# Thermostat_16CH.net
KiCad netlist of a schematic drawn in Altium Designer
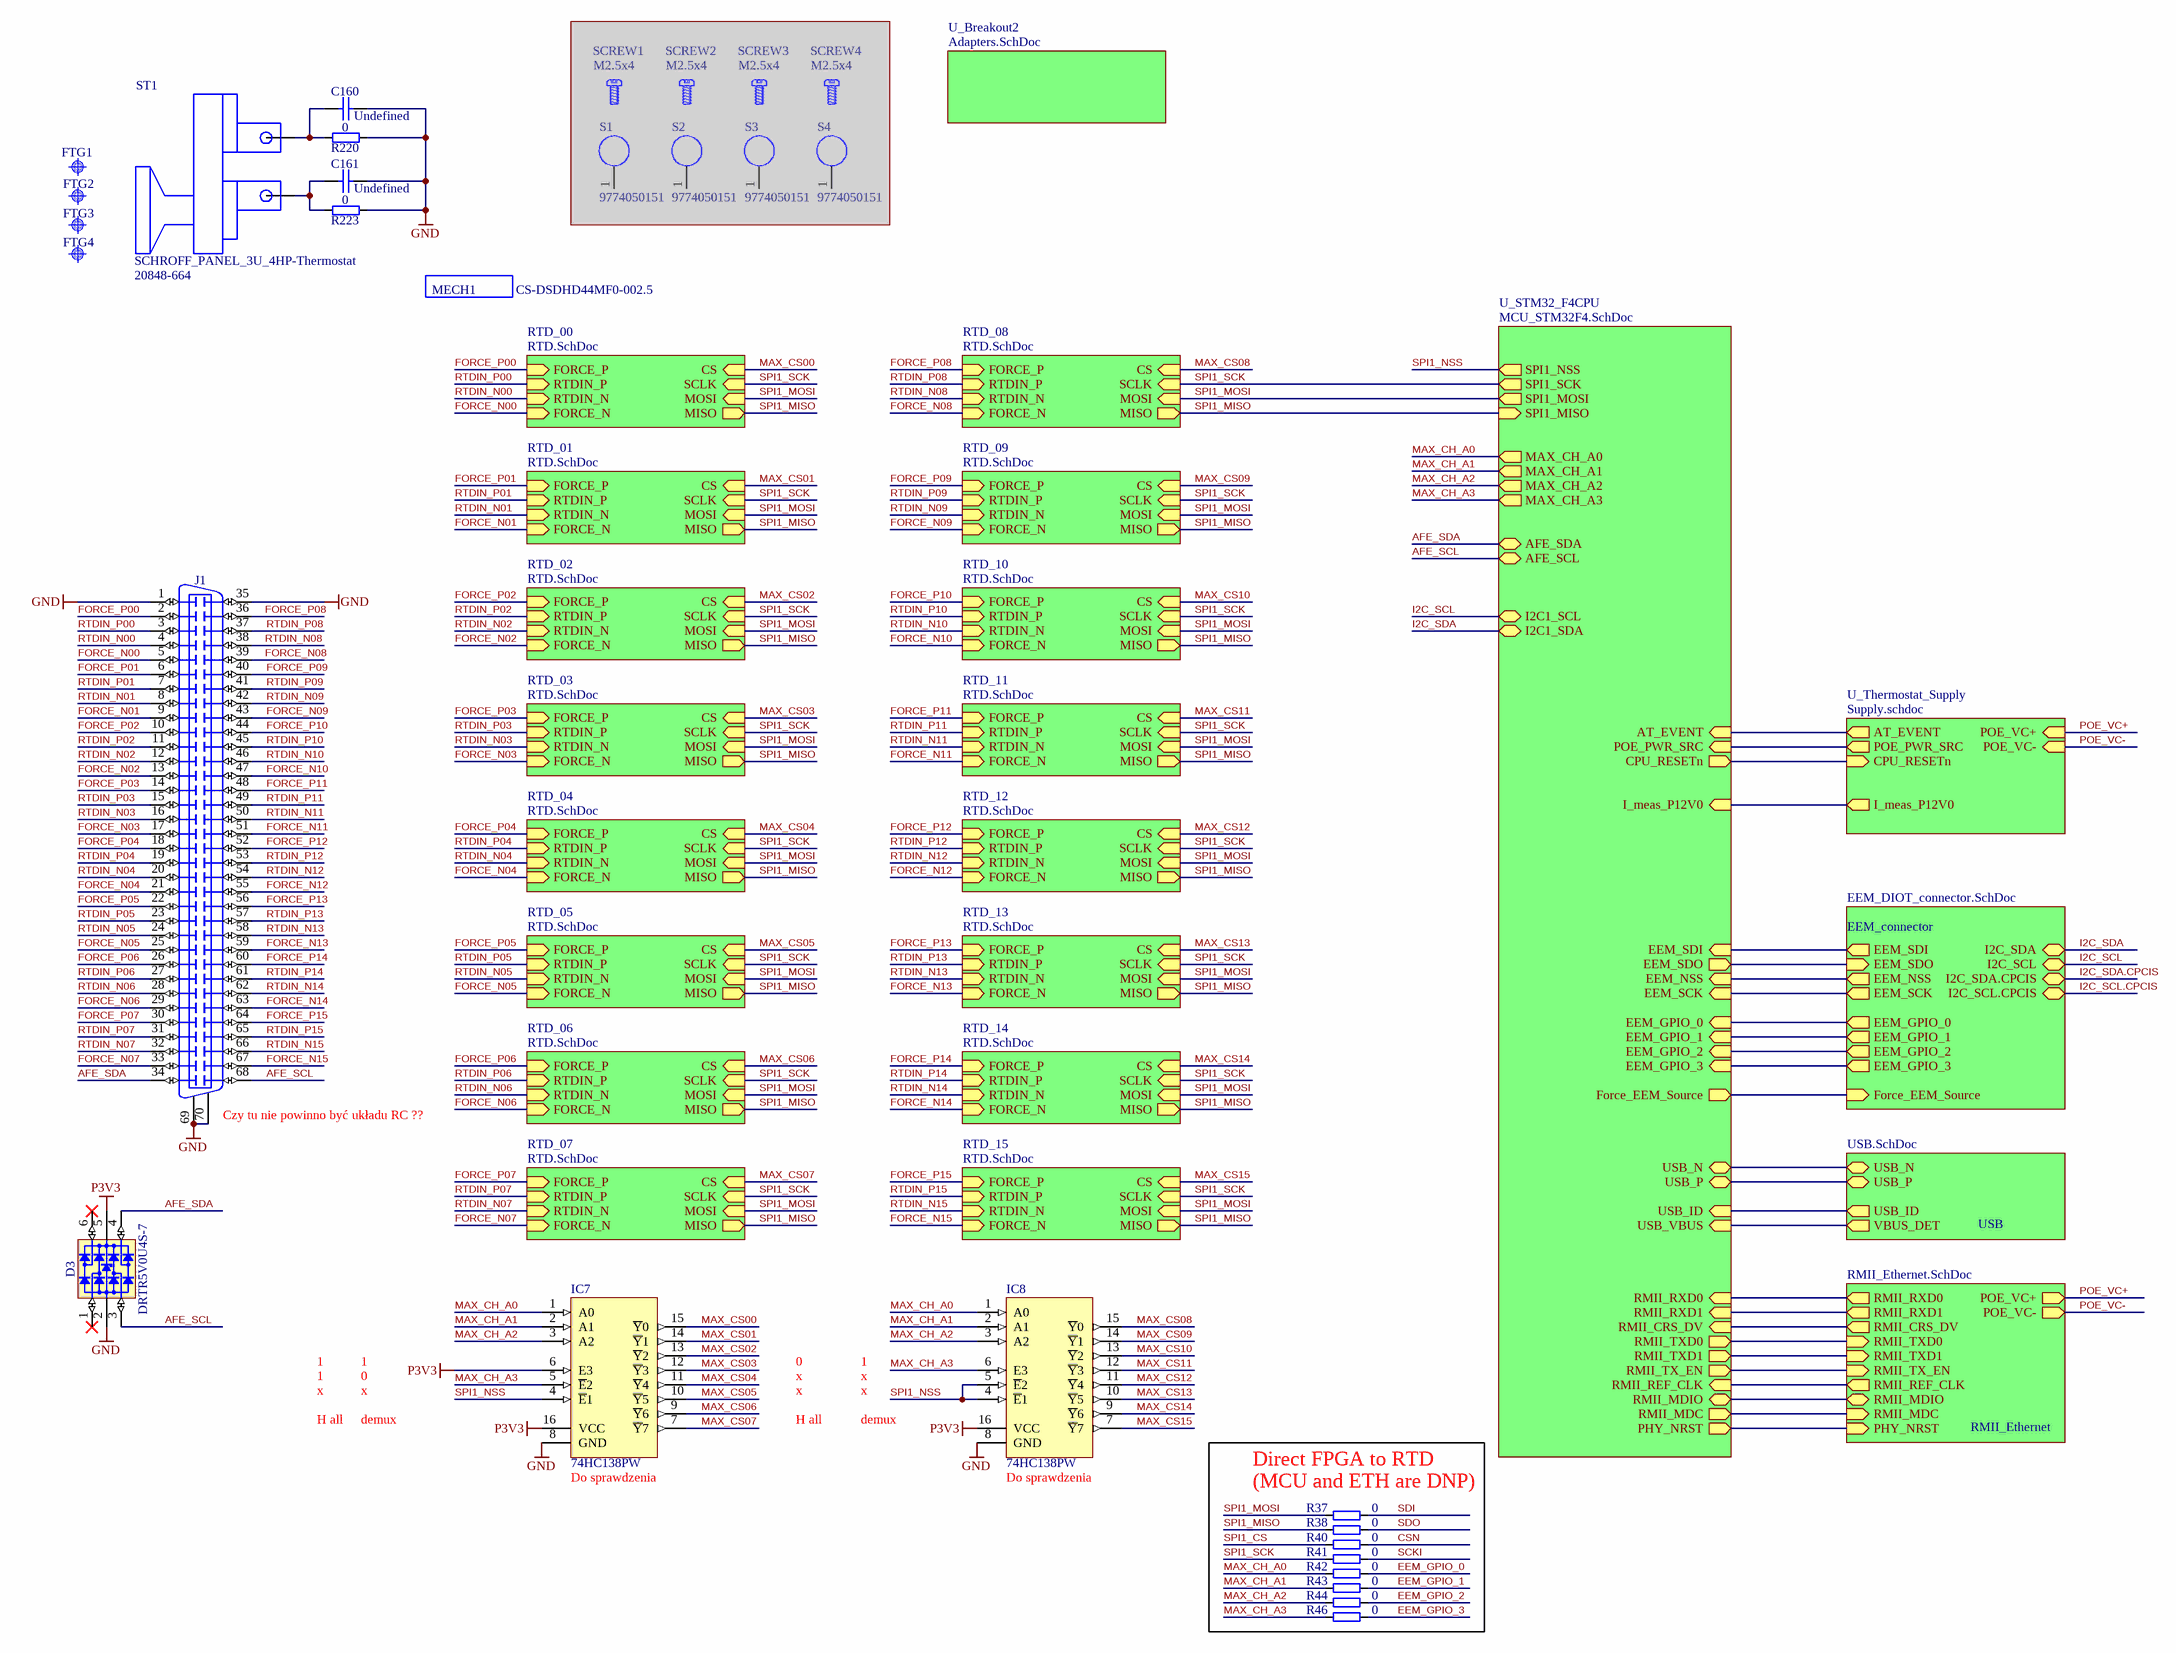
[diagram p0: Thermostat_16CH.SchDoc]

(export (version "E")
  (design (tool "Eeschema 10.0.6"))
  (components
    (comp (ref "C160")
      (value "Undefined")
      (footprint "CAPC2012X135N")
      (description "Non-polarised capacitor")
      (fields (field (name "PART NUMBER") "CC0805_NO-VALUE") (field (name "AUTHOR") "CERN DEM JLC"))
      (libsource (lib "Capacitors") (part "Capacitor - non polarized"))
    )
    (comp (ref "C161")
      (value "Undefined")
      (footprint "CAPC2012X135N")
      (description "Non-polarised capacitor")
      (fields (field (name "PART NUMBER") "CC0805_NO-VALUE") (field (name "AUTHOR") "CERN DEM JLC"))
      (libsource (lib "Capacitors") (part "Capacitor - non polarized"))
    )
    (comp (ref "D3")
      (value "DRTR5V0U4S-7")
      (footprint "SOT65P210X110-6N")
      (description "Integrated Quad Ultra-Low Capacitance ESD Protection")
      (fields (field (name "MANUFACTURER") "DIODES") (field (name "AUTHOR") "GK"))
      (libsource (lib "Diodes") (part "D_TVS_DRTR5V0U4S-7"))
    )
    (comp (ref "FTG1")
      (value "Use only in PCB")
      (footprint "FIDUCIAL_TOP_S100-200")
      (description "Fiducial Target")
      (fields (field (name "PART NUMBER") "FIDUCIAL_TARGET_S100-200") (field (name "AUTHOR") "CERN DEM JLC"))
      (libsource (lib "Eletro-mechanical") (part "Fiducial Target"))
    )
    (comp (ref "FTG2")
      (value "Use only in PCB")
      (footprint "FIDUCIAL_TOP_S100-200")
      (description "Fiducial Target")
      (fields (field (name "PART NUMBER") "FIDUCIAL_TARGET_S100-200") (field (name "AUTHOR") "CERN DEM JLC"))
      (libsource (lib "Eletro-mechanical") (part "Fiducial Target"))
    )
    (comp (ref "FTG3")
      (value "Use only in PCB")
      (footprint "FIDUCIAL_TOP_S100-200")
      (description "Fiducial Target")
      (fields (field (name "PART NUMBER") "FIDUCIAL_TARGET_S100-200") (field (name "AUTHOR") "CERN DEM JLC"))
      (libsource (lib "Eletro-mechanical") (part "Fiducial Target"))
    )
    (comp (ref "FTG4")
      (value "Use only in PCB")
      (footprint "FIDUCIAL_TOP_S100-200")
      (description "Fiducial Target")
      (fields (field (name "PART NUMBER") "FIDUCIAL_TARGET_S100-200") (field (name "AUTHOR") "CERN DEM JLC"))
      (libsource (lib "Eletro-mechanical") (part "Fiducial Target"))
    )
    (comp (ref "IC7")
      (value "74HC138PW")
      (footprint "SOP65P640X110-16N")
      (description "3-Line to 8-Line Decoder/Demultiplexer")
      (fields (field (name "MANUFACTURER") "NXP SEMICONDUCTORS") (field (name "AUTHOR") "CERN DEM JLC"))
      (libsource (lib "ICs And Semiconductors") (part "74138_a"))
    )
    (comp (ref "IC8")
      (value "74HC138PW")
      (footprint "SOP65P640X110-16N")
      (description "3-Line to 8-Line Decoder/Demultiplexer")
      (fields (field (name "MANUFACTURER") "NXP SEMICONDUCTORS") (field (name "AUTHOR") "CERN DEM JLC"))
      (libsource (lib "ICs And Semiconductors") (part "74138_a"))
    )
    (comp (ref "J1")
      (value "DNP")
      (footprint "MOLEX_71430-0013")
      (description "Very High Density Cable Interconnect (VHDCI ) 68 Female")
      (fields
        (field (name "PART NUMBER") "MOLEX_71430-0013")
        (field (name "MANUFACTURER") "MOLEX")
        (field (name "AUTHOR") "CERN DEM JLC")
      )
      (libsource (lib "FMC_DIO_32ch_lvds_a") (part "MOLEX_71430-0013"))
    )
    (comp (ref "MECH1")
      (value "CS-DSDHD44MF0-002.5")
      (description "D-Sub Cables DELUXE HD44 M/F MOLDED 2.5'")
      (fields (field (name "MANUFACTURER") "Amphenol") (field (name "AUTHOR") "GK"))
      (libsource (lib "Mechanical") (part "Generic_mechanical"))
    )
    (comp (ref "R37")
      (value "0")
      (footprint "RESC1608X55N")
      (description "Resistor")
      (fields
        (field (name "PART NUMBER") "R0603_0R_JUMPER")
        (field (name "MANUFACTURER") "GENERIC")
        (field (name "AUTHOR") "CERN DEM JLC")
      )
      (libsource (lib "Resistors") (part "Resistor"))
    )
    (comp (ref "R38")
      (value "0")
      (footprint "RESC1608X55N")
      (description "Resistor")
      (fields
        (field (name "PART NUMBER") "R0603_0R_JUMPER")
        (field (name "MANUFACTURER") "GENERIC")
        (field (name "AUTHOR") "CERN DEM JLC")
      )
      (libsource (lib "Resistors") (part "Resistor"))
    )
    (comp (ref "R40")
      (value "0")
      (footprint "RESC1608X55N")
      (description "Resistor")
      (fields
        (field (name "PART NUMBER") "R0603_0R_JUMPER")
        (field (name "MANUFACTURER") "GENERIC")
        (field (name "AUTHOR") "CERN DEM JLC")
      )
      (libsource (lib "Resistors") (part "Resistor"))
    )
    (comp (ref "R41")
      (value "0")
      (footprint "RESC1608X55N")
      (description "Resistor")
      (fields
        (field (name "PART NUMBER") "R0603_0R_JUMPER")
        (field (name "MANUFACTURER") "GENERIC")
        (field (name "AUTHOR") "CERN DEM JLC")
      )
      (libsource (lib "Resistors") (part "Resistor"))
    )
    (comp (ref "R42")
      (value "0")
      (footprint "RESC1608X55N")
      (description "Resistor")
      (fields
        (field (name "PART NUMBER") "R0603_0R_JUMPER")
        (field (name "MANUFACTURER") "GENERIC")
        (field (name "AUTHOR") "CERN DEM JLC")
      )
      (libsource (lib "Resistors") (part "Resistor"))
    )
    (comp (ref "R43")
      (value "0")
      (footprint "RESC1608X55N")
      (description "Resistor")
      (fields
        (field (name "PART NUMBER") "R0603_0R_JUMPER")
        (field (name "MANUFACTURER") "GENERIC")
        (field (name "AUTHOR") "CERN DEM JLC")
      )
      (libsource (lib "Resistors") (part "Resistor"))
    )
    (comp (ref "R44")
      (value "0")
      (footprint "RESC1608X55N")
      (description "Resistor")
      (fields
        (field (name "PART NUMBER") "R0603_0R_JUMPER")
        (field (name "MANUFACTURER") "GENERIC")
        (field (name "AUTHOR") "CERN DEM JLC")
      )
      (libsource (lib "Resistors") (part "Resistor"))
    )
    (comp (ref "R46")
      (value "0")
      (footprint "RESC1608X55N")
      (description "Resistor")
      (fields
        (field (name "PART NUMBER") "R0603_0R_JUMPER")
        (field (name "MANUFACTURER") "GENERIC")
        (field (name "AUTHOR") "CERN DEM JLC")
      )
      (libsource (lib "Resistors") (part "Resistor"))
    )
    (comp (ref "R220")
      (value "0")
      (footprint "RESC1608X55N")
      (description "Resistor")
      (fields
        (field (name "PART NUMBER") "R0603_0R_JUMPER")
        (field (name "MANUFACTURER") "GENERIC")
        (field (name "AUTHOR") "CERN DEM JLC")
      )
      (libsource (lib "Resistors") (part "Resistor"))
    )
    (comp (ref "R223")
      (value "0")
      (footprint "RESC1608X55N")
      (description "Resistor")
      (fields
        (field (name "PART NUMBER") "R0603_0R_JUMPER")
        (field (name "MANUFACTURER") "GENERIC")
        (field (name "AUTHOR") "CERN DEM JLC")
      )
      (libsource (lib "Resistors") (part "Resistor"))
    )
    (comp (ref "S1")
      (value "9774050151")
      (footprint "9774050151")
      (description "WA-SMSI SMD Steel Spacer with internal Thread")
      (fields (field (name "MANUFACTURER") "Wurth Elektronik") (field (name "CREATED BY") "Baojun Chen"))
      (libsource (lib "Altium_SMSI_SMT_STEEL_SPACER_M2_5_THREAD_INTERNAL_rev15a") (part "WA-SMSI,  9774050151"))
    )
    (comp (ref "S2")
      (value "9774050151")
      (footprint "9774050151")
      (description "WA-SMSI SMD Steel Spacer with internal Thread")
      (fields (field (name "MANUFACTURER") "Wurth Elektronik") (field (name "CREATED BY") "Baojun Chen"))
      (libsource (lib "Altium_SMSI_SMT_STEEL_SPACER_M2_5_THREAD_INTERNAL_rev15a") (part "WA-SMSI,  9774050151"))
    )
    (comp (ref "S3")
      (value "9774050151")
      (footprint "9774050151")
      (description "WA-SMSI SMD Steel Spacer with internal Thread")
      (fields (field (name "MANUFACTURER") "Wurth Elektronik") (field (name "CREATED BY") "Baojun Chen"))
      (libsource (lib "Altium_SMSI_SMT_STEEL_SPACER_M2_5_THREAD_INTERNAL_rev15a") (part "WA-SMSI,  9774050151"))
    )
    (comp (ref "S4")
      (value "9774050151")
      (footprint "9774050151")
      (description "WA-SMSI SMD Steel Spacer with internal Thread")
      (fields (field (name "MANUFACTURER") "Wurth Elektronik") (field (name "CREATED BY") "Baojun Chen"))
      (libsource (lib "Altium_SMSI_SMT_STEEL_SPACER_M2_5_THREAD_INTERNAL_rev15a") (part "WA-SMSI,  9774050151"))
    )
    (comp (ref "SCREW1")
      (value "M2.5x4")
      (footprint "BOSSARD_BN5687-3061587_v")
      (description "Screw")
      (fields
        (field (name "PART NUMBER") "BOSSARD_BN5687-3061587_v")
        (field (name "MANUFACTURER") "BOSSARD")
        (field (name "AUTHOR") "CERN DEM JLC")
      )
      (libsource (lib "Eletro-mechanical") (part "Screw"))
    )
    (comp (ref "SCREW2")
      (value "M2.5x4")
      (footprint "BOSSARD_BN5687-3061587_v")
      (description "Screw")
      (fields
        (field (name "PART NUMBER") "BOSSARD_BN5687-3061587_v")
        (field (name "MANUFACTURER") "BOSSARD")
        (field (name "AUTHOR") "CERN DEM JLC")
      )
      (libsource (lib "Eletro-mechanical") (part "Screw"))
    )
    (comp (ref "SCREW3")
      (value "M2.5x4")
      (footprint "BOSSARD_BN5687-3061587_v")
      (description "Screw")
      (fields
        (field (name "PART NUMBER") "BOSSARD_BN5687-3061587_v")
        (field (name "MANUFACTURER") "BOSSARD")
        (field (name "AUTHOR") "CERN DEM JLC")
      )
      (libsource (lib "Eletro-mechanical") (part "Screw"))
    )
    (comp (ref "SCREW4")
      (value "M2.5x4")
      (footprint "BOSSARD_BN5687-3061587_v")
      (description "Screw")
      (fields
        (field (name "PART NUMBER") "BOSSARD_BN5687-3061587_v")
        (field (name "MANUFACTURER") "BOSSARD")
        (field (name "AUTHOR") "CERN DEM JLC")
      )
      (libsource (lib "Eletro-mechanical") (part "Screw"))
    )
    (comp (ref "ST1")
      (value "SCHROFF_PANEL_3U_4HP-Thermostat")
      (footprint "SCHROFF_PANEL_3HP_4U - Thermostat")
      (description "Schroff 3HP 4U EUROCARD Panel")
      (fields
        (field (name "MANUFACTURER") "Schroff")
        (field (name "MANUFACTURER PART NUMBER") "20818-017")
        (field (name "MANUFACTURER PART NUMBER 2") "20848-664")
      )
      (libsource (lib "Mechanical") (part "SCHROFF_PANEL_3U_4HP_Thermostat"))
    )
  )
  (nets
    (net (code "1") (name "/AFE_SCL") (class "Default")
      (node (ref "D3") (pin "3") (pinfunction "I/O2_3") (pintype "bidirectional"))
      (node (ref "J1") (pin "68") (pinfunction "68_68") (pintype "bidirectional"))
    )
    (net (code "2") (name "/AFE_SDA") (class "Default")
      (node (ref "D3") (pin "4") (pinfunction "I/O3_4") (pintype "bidirectional"))
      (node (ref "J1") (pin "34") (pinfunction "34_34") (pintype "bidirectional"))
    )
    (net (code "5") (name "/CSN") (class "Default")
      (node (ref "R40") (pin "2") (pinfunction "2_2") (pintype "passive"))
    )
    (net (code "6") (name "/EEM_GPIO_0") (class "Default")
      (node (ref "R42") (pin "2") (pinfunction "2_2") (pintype "passive"))
    )
    (net (code "8") (name "/EEM_GPIO_1") (class "Default")
      (node (ref "R43") (pin "2") (pinfunction "2_2") (pintype "passive"))
    )
    (net (code "10") (name "/EEM_GPIO_2") (class "Default")
      (node (ref "R44") (pin "2") (pinfunction "2_2") (pintype "passive"))
    )
    (net (code "12") (name "/EEM_GPIO_3") (class "Default")
      (node (ref "R46") (pin "2") (pinfunction "2_2") (pintype "passive"))
    )
    (net (code "18") (name "/FORCE_N00") (class "Default")
      (node (ref "J1") (pin "5") (pinfunction "5_5") (pintype "bidirectional"))
    )
    (net (code "19") (name "/FORCE_N01") (class "Default")
      (node (ref "J1") (pin "9") (pinfunction "9_9") (pintype "bidirectional"))
    )
    (net (code "20") (name "/FORCE_N02") (class "Default")
      (node (ref "J1") (pin "13") (pinfunction "13_13") (pintype "bidirectional"))
    )
    (net (code "21") (name "/FORCE_N03") (class "Default")
      (node (ref "J1") (pin "17") (pinfunction "17_17") (pintype "bidirectional"))
    )
    (net (code "22") (name "/FORCE_N04") (class "Default")
      (node (ref "J1") (pin "21") (pinfunction "21_21") (pintype "bidirectional"))
    )
    (net (code "23") (name "/FORCE_N05") (class "Default")
      (node (ref "J1") (pin "25") (pinfunction "25_25") (pintype "bidirectional"))
    )
    (net (code "24") (name "/FORCE_N06") (class "Default")
      (node (ref "J1") (pin "29") (pinfunction "29_29") (pintype "bidirectional"))
    )
    (net (code "25") (name "/FORCE_N07") (class "Default")
      (node (ref "J1") (pin "33") (pinfunction "33_33") (pintype "bidirectional"))
    )
    (net (code "26") (name "/FORCE_N08") (class "Default")
      (node (ref "J1") (pin "39") (pinfunction "39_39") (pintype "bidirectional"))
    )
    (net (code "27") (name "/FORCE_N09") (class "Default")
      (node (ref "J1") (pin "43") (pinfunction "43_43") (pintype "bidirectional"))
    )
    (net (code "28") (name "/FORCE_N10") (class "Default")
      (node (ref "J1") (pin "47") (pinfunction "47_47") (pintype "bidirectional"))
    )
    (net (code "29") (name "/FORCE_N11") (class "Default")
      (node (ref "J1") (pin "51") (pinfunction "51_51") (pintype "bidirectional"))
    )
    (net (code "30") (name "/FORCE_N12") (class "Default")
      (node (ref "J1") (pin "55") (pinfunction "55_55") (pintype "bidirectional"))
    )
    (net (code "31") (name "/FORCE_N13") (class "Default")
      (node (ref "J1") (pin "59") (pinfunction "59_59") (pintype "bidirectional"))
    )
    (net (code "32") (name "/FORCE_N14") (class "Default")
      (node (ref "J1") (pin "63") (pinfunction "63_63") (pintype "bidirectional"))
    )
    (net (code "33") (name "/FORCE_N15") (class "Default")
      (node (ref "J1") (pin "67") (pinfunction "67_67") (pintype "bidirectional"))
    )
    (net (code "34") (name "/FORCE_P00") (class "Default")
      (node (ref "J1") (pin "2") (pinfunction "2_2") (pintype "bidirectional"))
    )
    (net (code "35") (name "/FORCE_P01") (class "Default")
      (node (ref "J1") (pin "6") (pinfunction "6_6") (pintype "bidirectional"))
    )
    (net (code "36") (name "/FORCE_P02") (class "Default")
      (node (ref "J1") (pin "10") (pinfunction "10_10") (pintype "bidirectional"))
    )
    (net (code "37") (name "/FORCE_P03") (class "Default")
      (node (ref "J1") (pin "14") (pinfunction "14_14") (pintype "bidirectional"))
    )
    (net (code "38") (name "/FORCE_P04") (class "Default")
      (node (ref "J1") (pin "18") (pinfunction "18_18") (pintype "bidirectional"))
    )
    (net (code "39") (name "/FORCE_P05") (class "Default")
      (node (ref "J1") (pin "22") (pinfunction "22_22") (pintype "bidirectional"))
    )
    (net (code "40") (name "/FORCE_P06") (class "Default")
      (node (ref "J1") (pin "26") (pinfunction "26_26") (pintype "bidirectional"))
    )
    (net (code "41") (name "/FORCE_P07") (class "Default")
      (node (ref "J1") (pin "30") (pinfunction "30_30") (pintype "bidirectional"))
    )
    (net (code "42") (name "/FORCE_P08") (class "Default")
      (node (ref "J1") (pin "36") (pinfunction "36_36") (pintype "bidirectional"))
    )
    (net (code "43") (name "/FORCE_P09") (class "Default")
      (node (ref "J1") (pin "40") (pinfunction "40_40") (pintype "bidirectional"))
    )
    (net (code "44") (name "/FORCE_P10") (class "Default")
      (node (ref "J1") (pin "44") (pinfunction "44_44") (pintype "bidirectional"))
    )
    (net (code "45") (name "/FORCE_P11") (class "Default")
      (node (ref "J1") (pin "48") (pinfunction "48_48") (pintype "bidirectional"))
    )
    (net (code "46") (name "/FORCE_P12") (class "Default")
      (node (ref "J1") (pin "52") (pinfunction "52_52") (pintype "bidirectional"))
    )
    (net (code "47") (name "/FORCE_P13") (class "Default")
      (node (ref "J1") (pin "56") (pinfunction "56_56") (pintype "bidirectional"))
    )
    (net (code "48") (name "/FORCE_P14") (class "Default")
      (node (ref "J1") (pin "60") (pinfunction "60_60") (pintype "bidirectional"))
    )
    (net (code "49") (name "/FORCE_P15") (class "Default")
      (node (ref "J1") (pin "64") (pinfunction "64_64") (pintype "bidirectional"))
    )
    (net (code "56") (name "/MAX_CH_A0") (class "Default")
      (node (ref "IC7") (pin "1") (pinfunction "A0_1") (pintype "input"))
      (node (ref "IC8") (pin "1") (pinfunction "A0_1") (pintype "input"))
      (node (ref "R42") (pin "1") (pinfunction "1_1") (pintype "passive"))
    )
    (net (code "57") (name "/MAX_CH_A1") (class "Default")
      (node (ref "IC7") (pin "2") (pinfunction "A1_2") (pintype "input"))
      (node (ref "IC8") (pin "2") (pinfunction "A1_2") (pintype "input"))
      (node (ref "R43") (pin "1") (pinfunction "1_1") (pintype "passive"))
    )
    (net (code "58") (name "/MAX_CH_A2") (class "Default")
      (node (ref "IC7") (pin "3") (pinfunction "A2_3") (pintype "input"))
      (node (ref "IC8") (pin "3") (pinfunction "A2_3") (pintype "input"))
      (node (ref "R44") (pin "1") (pinfunction "1_1") (pintype "passive"))
    )
    (net (code "59") (name "/MAX_CH_A3") (class "Default")
      (node (ref "IC7") (pin "5") (pinfunction "~{E}2_5") (pintype "input"))
      (node (ref "IC8") (pin "6") (pinfunction "E3_6") (pintype "input"))
      (node (ref "R46") (pin "1") (pinfunction "1_1") (pintype "passive"))
    )
    (net (code "60") (name "/MAX_CS00") (class "Default")
      (node (ref "IC7") (pin "15") (pinfunction "~{Y}0_15") (pintype "output"))
    )
    (net (code "61") (name "/MAX_CS01") (class "Default")
      (node (ref "IC7") (pin "14") (pinfunction "~{Y}1_14") (pintype "output"))
    )
    (net (code "62") (name "/MAX_CS02") (class "Default")
      (node (ref "IC7") (pin "13") (pinfunction "~{Y}2_13") (pintype "output"))
    )
    (net (code "63") (name "/MAX_CS03") (class "Default")
      (node (ref "IC7") (pin "12") (pinfunction "~{Y}3_12") (pintype "output"))
    )
    (net (code "64") (name "/MAX_CS04") (class "Default")
      (node (ref "IC7") (pin "11") (pinfunction "~{Y}4_11") (pintype "output"))
    )
    (net (code "65") (name "/MAX_CS05") (class "Default")
      (node (ref "IC7") (pin "10") (pinfunction "~{Y}5_10") (pintype "output"))
    )
    (net (code "66") (name "/MAX_CS06") (class "Default")
      (node (ref "IC7") (pin "9") (pinfunction "~{Y}6_9") (pintype "output"))
    )
    (net (code "67") (name "/MAX_CS07") (class "Default")
      (node (ref "IC7") (pin "7") (pinfunction "~{Y}7_7") (pintype "output"))
    )
    (net (code "68") (name "/MAX_CS08") (class "Default")
      (node (ref "IC8") (pin "15") (pinfunction "~{Y}0_15") (pintype "output"))
    )
    (net (code "69") (name "/MAX_CS09") (class "Default")
      (node (ref "IC8") (pin "14") (pinfunction "~{Y}1_14") (pintype "output"))
    )
    (net (code "70") (name "/MAX_CS10") (class "Default")
      (node (ref "IC8") (pin "13") (pinfunction "~{Y}2_13") (pintype "output"))
    )
    (net (code "71") (name "/MAX_CS11") (class "Default")
      (node (ref "IC8") (pin "12") (pinfunction "~{Y}3_12") (pintype "output"))
    )
    (net (code "72") (name "/MAX_CS12") (class "Default")
      (node (ref "IC8") (pin "11") (pinfunction "~{Y}4_11") (pintype "output"))
    )
    (net (code "73") (name "/MAX_CS13") (class "Default")
      (node (ref "IC8") (pin "10") (pinfunction "~{Y}5_10") (pintype "output"))
    )
    (net (code "74") (name "/MAX_CS14") (class "Default")
      (node (ref "IC8") (pin "9") (pinfunction "~{Y}6_9") (pintype "output"))
    )
    (net (code "75") (name "/MAX_CS15") (class "Default")
      (node (ref "IC8") (pin "7") (pinfunction "~{Y}7_7") (pintype "output"))
    )
    (net (code "89") (name "/RTDIN_N00") (class "Default")
      (node (ref "J1") (pin "4") (pinfunction "4_4") (pintype "bidirectional"))
    )
    (net (code "90") (name "/RTDIN_N01") (class "Default")
      (node (ref "J1") (pin "8") (pinfunction "8_8") (pintype "bidirectional"))
    )
    (net (code "91") (name "/RTDIN_N02") (class "Default")
      (node (ref "J1") (pin "12") (pinfunction "12_12") (pintype "bidirectional"))
    )
    (net (code "92") (name "/RTDIN_N03") (class "Default")
      (node (ref "J1") (pin "16") (pinfunction "16_16") (pintype "bidirectional"))
    )
    (net (code "93") (name "/RTDIN_N04") (class "Default")
      (node (ref "J1") (pin "20") (pinfunction "20_20") (pintype "bidirectional"))
    )
    (net (code "94") (name "/RTDIN_N05") (class "Default")
      (node (ref "J1") (pin "24") (pinfunction "24_24") (pintype "bidirectional"))
    )
    (net (code "95") (name "/RTDIN_N06") (class "Default")
      (node (ref "J1") (pin "28") (pinfunction "28_28") (pintype "bidirectional"))
    )
    (net (code "96") (name "/RTDIN_N07") (class "Default")
      (node (ref "J1") (pin "32") (pinfunction "32_32") (pintype "bidirectional"))
    )
    (net (code "97") (name "/RTDIN_N08") (class "Default")
      (node (ref "J1") (pin "38") (pinfunction "38_38") (pintype "bidirectional"))
    )
    (net (code "98") (name "/RTDIN_N09") (class "Default")
      (node (ref "J1") (pin "42") (pinfunction "42_42") (pintype "bidirectional"))
    )
    (net (code "99") (name "/RTDIN_N10") (class "Default")
      (node (ref "J1") (pin "46") (pinfunction "46_46") (pintype "bidirectional"))
    )
    (net (code "100") (name "/RTDIN_N11") (class "Default")
      (node (ref "J1") (pin "50") (pinfunction "50_50") (pintype "bidirectional"))
    )
    (net (code "101") (name "/RTDIN_N12") (class "Default")
      (node (ref "J1") (pin "54") (pinfunction "54_54") (pintype "bidirectional"))
    )
    (net (code "102") (name "/RTDIN_N13") (class "Default")
      (node (ref "J1") (pin "58") (pinfunction "58_58") (pintype "bidirectional"))
    )
    (net (code "103") (name "/RTDIN_N14") (class "Default")
      (node (ref "J1") (pin "62") (pinfunction "62_62") (pintype "bidirectional"))
    )
    (net (code "104") (name "/RTDIN_N15") (class "Default")
      (node (ref "J1") (pin "66") (pinfunction "66_66") (pintype "bidirectional"))
    )
    (net (code "105") (name "/RTDIN_P00") (class "Default")
      (node (ref "J1") (pin "3") (pinfunction "3_3") (pintype "bidirectional"))
    )
    (net (code "106") (name "/RTDIN_P01") (class "Default")
      (node (ref "J1") (pin "7") (pinfunction "7_7") (pintype "bidirectional"))
    )
    (net (code "107") (name "/RTDIN_P02") (class "Default")
      (node (ref "J1") (pin "11") (pinfunction "11_11") (pintype "bidirectional"))
    )
    (net (code "108") (name "/RTDIN_P03") (class "Default")
      (node (ref "J1") (pin "15") (pinfunction "15_15") (pintype "bidirectional"))
    )
    (net (code "109") (name "/RTDIN_P04") (class "Default")
      (node (ref "J1") (pin "19") (pinfunction "19_19") (pintype "bidirectional"))
    )
    (net (code "110") (name "/RTDIN_P05") (class "Default")
      (node (ref "J1") (pin "23") (pinfunction "23_23") (pintype "bidirectional"))
    )
    (net (code "111") (name "/RTDIN_P06") (class "Default")
      (node (ref "J1") (pin "27") (pinfunction "27_27") (pintype "bidirectional"))
    )
    (net (code "112") (name "/RTDIN_P07") (class "Default")
      (node (ref "J1") (pin "31") (pinfunction "31_31") (pintype "bidirectional"))
    )
    (net (code "113") (name "/RTDIN_P08") (class "Default")
      (node (ref "J1") (pin "37") (pinfunction "37_37") (pintype "bidirectional"))
    )
    (net (code "114") (name "/RTDIN_P09") (class "Default")
      (node (ref "J1") (pin "41") (pinfunction "41_41") (pintype "bidirectional"))
    )
    (net (code "115") (name "/RTDIN_P10") (class "Default")
      (node (ref "J1") (pin "45") (pinfunction "45_45") (pintype "bidirectional"))
    )
    (net (code "116") (name "/RTDIN_P11") (class "Default")
      (node (ref "J1") (pin "49") (pinfunction "49_49") (pintype "bidirectional"))
    )
    (net (code "117") (name "/RTDIN_P12") (class "Default")
      (node (ref "J1") (pin "53") (pinfunction "53_53") (pintype "bidirectional"))
    )
    (net (code "118") (name "/RTDIN_P13") (class "Default")
      (node (ref "J1") (pin "57") (pinfunction "57_57") (pintype "bidirectional"))
    )
    (net (code "119") (name "/RTDIN_P14") (class "Default")
      (node (ref "J1") (pin "61") (pinfunction "61_61") (pintype "bidirectional"))
    )
    (net (code "120") (name "/RTDIN_P15") (class "Default")
      (node (ref "J1") (pin "65") (pinfunction "65_65") (pintype "bidirectional"))
    )
    (net (code "121") (name "/SCKI") (class "Default")
      (node (ref "R41") (pin "2") (pinfunction "2_2") (pintype "passive"))
    )
    (net (code "122") (name "/SDI") (class "Default")
      (node (ref "R37") (pin "2") (pinfunction "2_2") (pintype "passive"))
    )
    (net (code "123") (name "/SDO") (class "Default")
      (node (ref "R38") (pin "2") (pinfunction "2_2") (pintype "passive"))
    )
    (net (code "124") (name "/SPI1_CS") (class "Default")
      (node (ref "R40") (pin "1") (pinfunction "1_1") (pintype "passive"))
    )
    (net (code "125") (name "/SPI1_MISO") (class "Default")
      (node (ref "R38") (pin "1") (pinfunction "1_1") (pintype "passive"))
    )
    (net (code "126") (name "/SPI1_MOSI") (class "Default")
      (node (ref "R37") (pin "1") (pinfunction "1_1") (pintype "passive"))
    )
    (net (code "127") (name "/SPI1_NSS") (class "Default")
      (node (ref "IC7") (pin "4") (pinfunction "~{E}1_4") (pintype "input"))
      (node (ref "IC8") (pin "4") (pinfunction "~{E}1_4") (pintype "input"))
      (node (ref "IC8") (pin "5") (pinfunction "~{E}2_5") (pintype "input"))
    )
    (net (code "128") (name "/SPI1_SCK") (class "Default")
      (node (ref "R41") (pin "1") (pinfunction "1_1") (pintype "passive"))
    )
    (net (code "133") (name "GND") (class "Default")
      (node (ref "C160") (pin "2") (pinfunction "2_2") (pintype "passive"))
      (node (ref "C161") (pin "2") (pinfunction "2_2") (pintype "passive"))
      (node (ref "D3") (pin "2") (pinfunction "GND_2") (pintype "power_in"))
      (node (ref "IC7") (pin "8") (pinfunction "GND_8") (pintype "power_in"))
      (node (ref "IC8") (pin "8") (pinfunction "GND_8") (pintype "power_in"))
      (node (ref "J1") (pin "1") (pinfunction "1_1") (pintype "bidirectional"))
      (node (ref "J1") (pin "35") (pinfunction "35_35") (pintype "bidirectional"))
      (node (ref "J1") (pin "69") (pinfunction "69_69") (pintype "passive"))
      (node (ref "J1") (pin "70") (pinfunction "70_70") (pintype "passive"))
      (node (ref "R220") (pin "1") (pinfunction "1_1") (pintype "passive"))
      (node (ref "R223") (pin "1") (pinfunction "1_1") (pintype "passive"))
    )
    (net (code "134") (name "Net-(C160-Pad1)") (class "Default")
      (node (ref "C160") (pin "1") (pinfunction "1_1") (pintype "passive"))
      (node (ref "R220") (pin "2") (pinfunction "2_2") (pintype "passive"))
      (node (ref "ST1") (pin "1") (pinfunction "1_1") (pintype "passive"))
    )
    (net (code "135") (name "Net-(C161-Pad1)") (class "Default")
      (node (ref "C161") (pin "1") (pinfunction "1_1") (pintype "passive"))
      (node (ref "R223") (pin "2") (pinfunction "2_2") (pintype "passive"))
      (node (ref "ST1") (pin "0") (pinfunction "0_0") (pintype "passive"))
    )
    (net (code "136") (name "P3V3") (class "Default")
      (node (ref "D3") (pin "5") (pinfunction "VBUS_5") (pintype "power_in"))
      (node (ref "IC7") (pin "16") (pinfunction "VCC_16") (pintype "power_in"))
      (node (ref "IC7") (pin "6") (pinfunction "E3_6") (pintype "input"))
      (node (ref "IC8") (pin "16") (pinfunction "VCC_16") (pintype "power_in"))
    )
    (net (code "137") (name "unconnected-(D3-I{slash}O1-Pad1)") (class "Default")
      (node (ref "D3") (pin "1") (pinfunction "I/O1_1") (pintype "bidirectional+no_connect"))
    )
    (net (code "138") (name "unconnected-(D3-I{slash}O4-Pad6)") (class "Default")
      (node (ref "D3") (pin "6") (pinfunction "I/O4_6") (pintype "bidirectional+no_connect"))
    )
    (net (code "139") (name "unconnected-(S1-Pad1)") (class "Default")
      (node (ref "S1") (pin "1") (pinfunction "1_1") (pintype "passive"))
    )
    (net (code "140") (name "unconnected-(S2-Pad1)") (class "Default")
      (node (ref "S2") (pin "1") (pinfunction "1_1") (pintype "passive"))
    )
    (net (code "141") (name "unconnected-(S3-Pad1)") (class "Default")
      (node (ref "S3") (pin "1") (pinfunction "1_1") (pintype "passive"))
    )
    (net (code "142") (name "unconnected-(S4-Pad1)") (class "Default")
      (node (ref "S4") (pin "1") (pinfunction "1_1") (pintype "passive"))
    )
  )
)
